# mother_bord.net
KiCad netlist of a schematic drawn in EAGLE
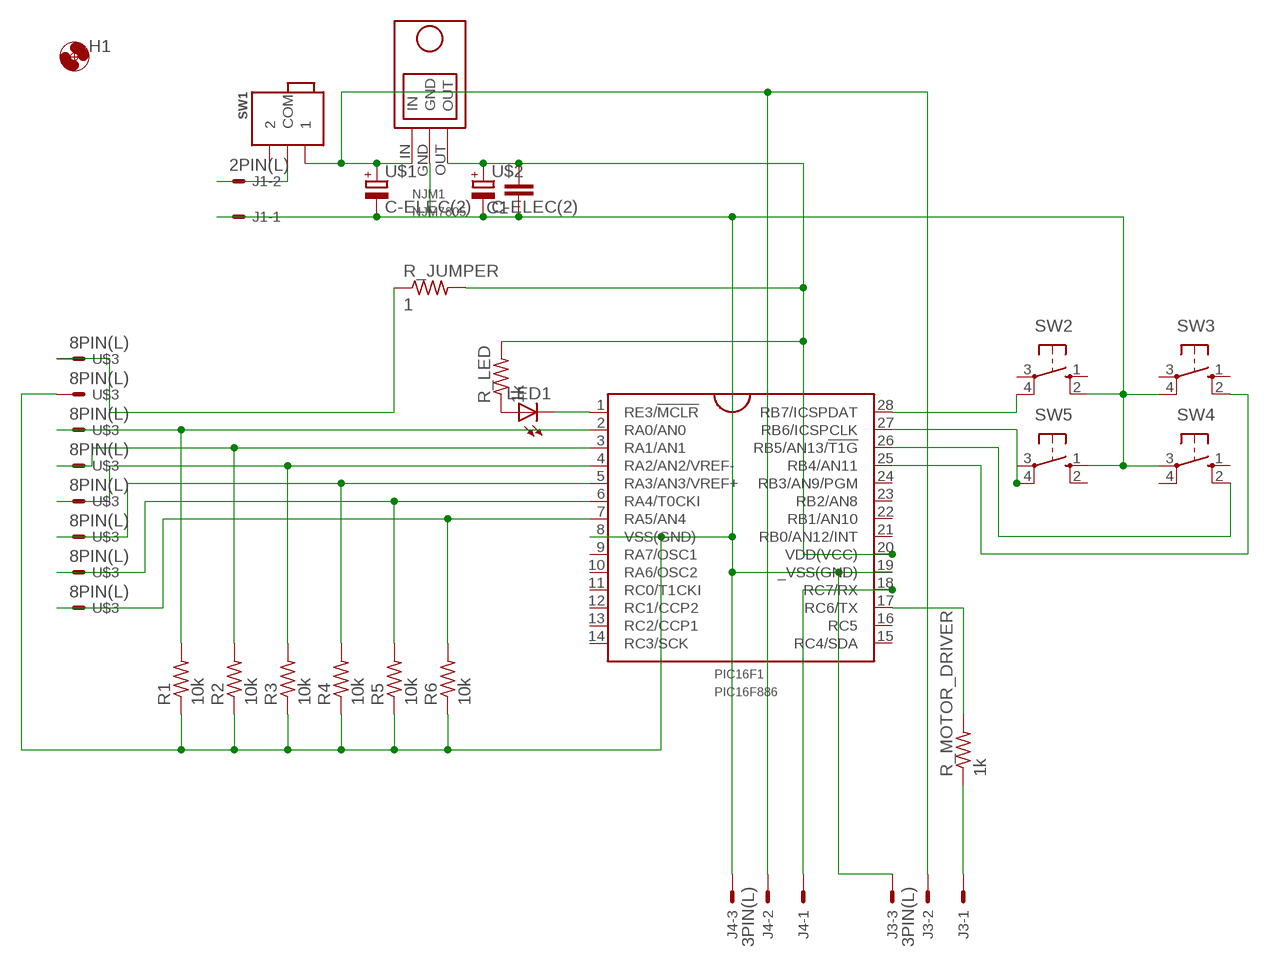
[diagram p0: schematic, sheet 1]

(export (version "E")
  (design (tool "Eeschema 10.0.6"))
  (components
    (comp (ref "C1")
      (value "C-3")
      (footprint "eagle-import:C-3")
      (libsource (lib "eagle-import") (part "C-3"))
    )
    (comp (ref "H1")
      (value "HOLE3.3M3BOLT")
      (footprint "eagle-import:HOLE3.3")
      (libsource (lib "eagle-import") (part "HOLE3.3M3BOLT"))
    )
    (comp (ref "J1")
      (value "2PIN(L)")
      (footprint "eagle-import:2PL")
      (libsource (lib "eagle-import") (part "2PIN(L)"))
    )
    (comp (ref "J3")
      (value "3PIN(L)")
      (footprint "eagle-import:3PL")
      (libsource (lib "eagle-import") (part "3PIN(L)"))
    )
    (comp (ref "J4")
      (value "3PIN(L)")
      (footprint "eagle-import:3PL")
      (libsource (lib "eagle-import") (part "3PIN(L)"))
    )
    (comp (ref "LED1")
      (value "LED-2")
      (footprint "eagle-import:LED5MM-2")
      (libsource (lib "eagle-import") (part "LED-2"))
    )
    (comp (ref "NJM1")
      (value "NJM7805")
      (footprint "eagle-import:NJM7805")
      (libsource (lib "eagle-import") (part "NJM7805"))
    )
    (comp (ref "PIC16F1")
      (value "PIC16F886")
      (footprint "eagle-import:DIL28-3")
      (libsource (lib "eagle-import") (part "PIC16F886"))
    )
    (comp (ref "R1")
      (value "10k")
      (footprint "eagle-import:0207_10")
      (libsource (lib "eagle-import") (part "R-"))
    )
    (comp (ref "R2")
      (value "10k")
      (footprint "eagle-import:0207_10")
      (libsource (lib "eagle-import") (part "R-"))
    )
    (comp (ref "R3")
      (value "10k")
      (footprint "eagle-import:0207_10")
      (libsource (lib "eagle-import") (part "R-"))
    )
    (comp (ref "R4")
      (value "10k")
      (footprint "eagle-import:0207_10")
      (libsource (lib "eagle-import") (part "R-"))
    )
    (comp (ref "R5")
      (value "10k")
      (footprint "eagle-import:0207_10")
      (libsource (lib "eagle-import") (part "R-"))
    )
    (comp (ref "R6")
      (value "10k")
      (footprint "eagle-import:0207_10")
      (libsource (lib "eagle-import") (part "R-"))
    )
    (comp (ref "R_JUMPER")
      (value "1")
      (footprint "eagle-import:0207_10")
      (libsource (lib "eagle-import") (part "R-"))
    )
    (comp (ref "R_LED")
      (value "1k")
      (footprint "eagle-import:0207_10")
      (libsource (lib "eagle-import") (part "R-"))
    )
    (comp (ref "R_MOTOR_DRIVER")
      (value "1k")
      (footprint "eagle-import:0207_10")
      (libsource (lib "eagle-import") (part "R-"))
    )
    (comp (ref "SW1")
      (value "SWITCH_MININORMAL")
      (footprint "eagle-import:SWITCH_MINI")
      (libsource (lib "eagle-import") (part "SWITCH_MININORMAL"))
    )
    (comp (ref "SW2")
      (value "TACTSW")
      (footprint "eagle-import:TACT")
      (libsource (lib "eagle-import") (part "TACTSW"))
    )
    (comp (ref "SW3")
      (value "TACTSW")
      (footprint "eagle-import:TACT")
      (libsource (lib "eagle-import") (part "TACTSW"))
    )
    (comp (ref "SW4")
      (value "TACTSW")
      (footprint "eagle-import:TACT")
      (libsource (lib "eagle-import") (part "TACTSW"))
    )
    (comp (ref "SW5")
      (value "TACTSW")
      (footprint "eagle-import:TACT")
      (libsource (lib "eagle-import") (part "TACTSW"))
    )
    (comp (ref "U$1")
      (value "C-ELEC(2)")
      (footprint "eagle-import:C-6MM(2)")
      (libsource (lib "eagle-import") (part "C-ELEC(2)"))
    )
    (comp (ref "U$2")
      (value "C-ELEC(2)")
      (footprint "eagle-import:C-6MM(2)")
      (libsource (lib "eagle-import") (part "C-ELEC(2)"))
    )
    (comp (ref "U$3")
      (value "8PIN(L)")
      (footprint "eagle-import:8PL")
      (libsource (lib "eagle-import") (part "8PIN(L)"))
    )
  )
  (nets
    (net (code "1") (name "/9V") (class "Default")
      (node (ref "J1") (pin "2") (pinfunction "S_2") (pintype "passive"))
      (node (ref "J3") (pin "2") (pinfunction "S_2") (pintype "passive"))
      (node (ref "J4") (pin "2") (pinfunction "S_2") (pintype "passive"))
      (node (ref "NJM1") (pin "IN") (pinfunction "IN_IN") (pintype "bidirectional"))
      (node (ref "SW1") (pin "1") (pinfunction "1_1") (pintype "passive"))
      (node (ref "SW1") (pin "COM") (pinfunction "COM_COM") (pintype "passive"))
      (node (ref "U$1") (pin "+") (pinfunction "+_+") (pintype "passive"))
    )
    (net (code "2") (name "Net-(J1A-S)") (class "Default")
      (node (ref "C1") (pin "1") (pinfunction "1_1") (pintype "passive"))
      (node (ref "J1") (pin "1") (pinfunction "S_1") (pintype "passive"))
      (node (ref "J3") (pin "3") (pinfunction "S_3") (pintype "passive"))
      (node (ref "J4") (pin "3") (pinfunction "S_3") (pintype "passive"))
      (node (ref "NJM1") (pin "GND") (pinfunction "GND_GND") (pintype "bidirectional"))
      (node (ref "PIC16F1") (pin "19") (pinfunction "_VSS(GND)_19") (pintype "power_in"))
      (node (ref "PIC16F1") (pin "8") (pinfunction "VSS(GND)_8") (pintype "power_in"))
      (node (ref "R1") (pin "1") (pinfunction "1_1") (pintype "passive"))
      (node (ref "R2") (pin "1") (pinfunction "1_1") (pintype "passive"))
      (node (ref "R3") (pin "1") (pinfunction "1_1") (pintype "passive"))
      (node (ref "R4") (pin "1") (pinfunction "1_1") (pintype "passive"))
      (node (ref "R5") (pin "1") (pinfunction "1_1") (pintype "passive"))
      (node (ref "R6") (pin "1") (pinfunction "1_1") (pintype "passive"))
      (node (ref "SW2") (pin "2") (pinfunction "S1_2") (pintype "passive"))
      (node (ref "SW3") (pin "4") (pinfunction "P1_4") (pintype "passive"))
      (node (ref "SW4") (pin "3") (pinfunction "P_3") (pintype "passive"))
      (node (ref "SW5") (pin "1") (pinfunction "S_1") (pintype "passive"))
      (node (ref "U$1") (pin "-") (pinfunction "-_-") (pintype "passive"))
      (node (ref "U$2") (pin "-") (pinfunction "-_-") (pintype "passive"))
      (node (ref "U$3") (pin "P7") (pinfunction "P7_P7") (pintype "passive"))
    )
    (net (code "3") (name "Net-(J3A-S)") (class "Default")
      (node (ref "J3") (pin "1") (pinfunction "S_1") (pintype "passive"))
      (node (ref "R_MOTOR_DRIVER") (pin "1") (pinfunction "1_1") (pintype "passive"))
    )
    (net (code "4") (name "Net-(J4A-S)") (class "Default")
      (node (ref "J4") (pin "1") (pinfunction "S_1") (pintype "passive"))
      (node (ref "PIC16F1") (pin "18") (pinfunction "RC7/RX_18") (pintype "bidirectional"))
    )
    (net (code "5") (name "Net-(LED1-C)") (class "Default")
      (node (ref "LED1") (pin "K") (pinfunction "C_K") (pintype "passive"))
      (node (ref "PIC16F1") (pin "1") (pinfunction "RE3/~{MCLR}_1") (pintype "bidirectional"))
    )
    (net (code "6") (name "Net-(LED1-PadA)") (class "Default")
      (node (ref "LED1") (pin "A") (pinfunction "A_A") (pintype "passive"))
      (node (ref "R_LED") (pin "1") (pinfunction "1_1") (pintype "passive"))
    )
    (net (code "7") (name "Net-(PIC16F1-RA0{slash}AN0)") (class "Default")
      (node (ref "PIC16F1") (pin "2") (pinfunction "RA0/AN0_2") (pintype "bidirectional"))
      (node (ref "R1") (pin "2") (pinfunction "2_2") (pintype "passive"))
      (node (ref "U$3") (pin "P6") (pinfunction "P6_P6") (pintype "passive"))
    )
    (net (code "8") (name "Net-(PIC16F1-RA1{slash}AN1)") (class "Default")
      (node (ref "PIC16F1") (pin "3") (pinfunction "RA1/AN1_3") (pintype "bidirectional"))
      (node (ref "R2") (pin "2") (pinfunction "2_2") (pintype "passive"))
      (node (ref "U$3") (pin "P5") (pinfunction "P5_P5") (pintype "passive"))
    )
    (net (code "9") (name "Net-(PIC16F1-RA2{slash}AN2{slash}VREF-)") (class "Default")
      (node (ref "PIC16F1") (pin "4") (pinfunction "RA2/AN2/VREF-_4") (pintype "bidirectional"))
      (node (ref "R3") (pin "2") (pinfunction "2_2") (pintype "passive"))
      (node (ref "U$3") (pin "P4") (pinfunction "P4_P4") (pintype "passive"))
    )
    (net (code "10") (name "Net-(PIC16F1-RA3{slash}AN3{slash}VREF+)") (class "Default")
      (node (ref "PIC16F1") (pin "5") (pinfunction "RA3/AN3/VREF+_5") (pintype "bidirectional"))
      (node (ref "R4") (pin "2") (pinfunction "2_2") (pintype "passive"))
      (node (ref "U$3") (pin "P3") (pinfunction "P3_P3") (pintype "passive"))
    )
    (net (code "11") (name "Net-(PIC16F1-RA4{slash}T0CKI)") (class "Default")
      (node (ref "PIC16F1") (pin "6") (pinfunction "RA4/T0CKI_6") (pintype "bidirectional"))
      (node (ref "R5") (pin "2") (pinfunction "2_2") (pintype "passive"))
      (node (ref "U$3") (pin "P2") (pinfunction "P2_P2") (pintype "passive"))
    )
    (net (code "12") (name "Net-(PIC16F1-RA5{slash}AN4)") (class "Default")
      (node (ref "PIC16F1") (pin "7") (pinfunction "RA5/AN4_7") (pintype "bidirectional"))
      (node (ref "R6") (pin "2") (pinfunction "2_2") (pintype "passive"))
      (node (ref "U$3") (pin "P1") (pinfunction "P1_P1") (pintype "passive"))
    )
    (net (code "13") (name "Net-(PIC16F1-RB4{slash}AN11)") (class "Default")
      (node (ref "PIC16F1") (pin "25") (pinfunction "RB4/AN11_25") (pintype "bidirectional"))
      (node (ref "SW3") (pin "2") (pinfunction "S1_2") (pintype "passive"))
    )
    (net (code "14") (name "Net-(PIC16F1-RB5{slash}AN13{slash}~{T1G})") (class "Default")
      (node (ref "PIC16F1") (pin "26") (pinfunction "RB5/AN13/~{T1G}_26") (pintype "bidirectional"))
      (node (ref "SW4") (pin "2") (pinfunction "S1_2") (pintype "passive"))
    )
    (net (code "15") (name "Net-(PIC16F1-RB6{slash}ICSPCLK)") (class "Default")
      (node (ref "PIC16F1") (pin "27") (pinfunction "RB6/ICSPCLK_27") (pintype "bidirectional"))
      (node (ref "SW5") (pin "4") (pinfunction "P1_4") (pintype "passive"))
    )
    (net (code "16") (name "Net-(PIC16F1-RB7{slash}ICSPDAT)") (class "Default")
      (node (ref "PIC16F1") (pin "28") (pinfunction "RB7/ICSPDAT_28") (pintype "bidirectional"))
      (node (ref "SW2") (pin "4") (pinfunction "P1_4") (pintype "passive"))
    )
    (net (code "17") (name "Net-(PIC16F1-RC6{slash}TX)") (class "Default")
      (node (ref "PIC16F1") (pin "17") (pinfunction "RC6/TX_17") (pintype "bidirectional"))
      (node (ref "R_MOTOR_DRIVER") (pin "2") (pinfunction "2_2") (pintype "passive"))
    )
    (net (code "18") (name "Net-(PIC16F1-VDD(VCC))") (class "Default")
      (node (ref "C1") (pin "2") (pinfunction "2_2") (pintype "passive"))
      (node (ref "NJM1") (pin "OUT") (pinfunction "OUT_OUT") (pintype "bidirectional"))
      (node (ref "PIC16F1") (pin "20") (pinfunction "VDD(VCC)_20") (pintype "power_in"))
      (node (ref "R_JUMPER") (pin "2") (pinfunction "2_2") (pintype "passive"))
      (node (ref "R_LED") (pin "2") (pinfunction "2_2") (pintype "passive"))
      (node (ref "U$2") (pin "+") (pinfunction "+_+") (pintype "passive"))
    )
    (net (code "19") (name "Net-(R_JUMPER-Pad1)") (class "Default")
      (node (ref "R_JUMPER") (pin "1") (pinfunction "1_1") (pintype "passive"))
      (node (ref "U$3") (pin "P8") (pinfunction "P8_P8") (pintype "passive"))
    )
    (net (code "20") (name "unconnected-(PIC16F1-RA6{slash}OSC2-Pad10)") (class "Default")
      (node (ref "PIC16F1") (pin "10") (pinfunction "RA6/OSC2_10") (pintype "bidirectional"))
    )
    (net (code "21") (name "unconnected-(PIC16F1-RA7{slash}OSC1-Pad9)") (class "Default")
      (node (ref "PIC16F1") (pin "9") (pinfunction "RA7/OSC1_9") (pintype "bidirectional"))
    )
    (net (code "22") (name "unconnected-(PIC16F1-RB0{slash}AN12{slash}INT-Pad21)") (class "Default")
      (node (ref "PIC16F1") (pin "21") (pinfunction "RB0/AN12/INT_21") (pintype "bidirectional"))
    )
    (net (code "23") (name "unconnected-(PIC16F1-RB1{slash}AN10-Pad22)") (class "Default")
      (node (ref "PIC16F1") (pin "22") (pinfunction "RB1/AN10_22") (pintype "bidirectional"))
    )
    (net (code "24") (name "unconnected-(PIC16F1-RB2{slash}AN8-Pad23)") (class "Default")
      (node (ref "PIC16F1") (pin "23") (pinfunction "RB2/AN8_23") (pintype "bidirectional"))
    )
    (net (code "25") (name "unconnected-(PIC16F1-RB3{slash}AN9{slash}PGM-Pad24)") (class "Default")
      (node (ref "PIC16F1") (pin "24") (pinfunction "RB3/AN9/PGM_24") (pintype "bidirectional"))
    )
    (net (code "26") (name "unconnected-(PIC16F1-RC0{slash}T1CKI-Pad11)") (class "Default")
      (node (ref "PIC16F1") (pin "11") (pinfunction "RC0/T1CKI_11") (pintype "bidirectional"))
    )
    (net (code "27") (name "unconnected-(PIC16F1-RC1{slash}CCP2-Pad12)") (class "Default")
      (node (ref "PIC16F1") (pin "12") (pinfunction "RC1/CCP2_12") (pintype "bidirectional"))
    )
    (net (code "28") (name "unconnected-(PIC16F1-RC2{slash}CCP1-Pad13)") (class "Default")
      (node (ref "PIC16F1") (pin "13") (pinfunction "RC2/CCP1_13") (pintype "bidirectional"))
    )
    (net (code "29") (name "unconnected-(PIC16F1-RC3{slash}SCK-Pad14)") (class "Default")
      (node (ref "PIC16F1") (pin "14") (pinfunction "RC3/SCK_14") (pintype "bidirectional"))
    )
    (net (code "30") (name "unconnected-(PIC16F1-RC4{slash}SDA-Pad15)") (class "Default")
      (node (ref "PIC16F1") (pin "15") (pinfunction "RC4/SDA_15") (pintype "bidirectional"))
    )
    (net (code "31") (name "unconnected-(PIC16F1-RC5-Pad16)") (class "Default")
      (node (ref "PIC16F1") (pin "16") (pinfunction "RC5_16") (pintype "bidirectional"))
    )
    (net (code "32") (name "unconnected-(SW1-Pad2)") (class "Default")
      (node (ref "SW1") (pin "2") (pinfunction "2_2") (pintype "no_connect"))
    )
    (net (code "33") (name "unconnected-(SW2-P-Pad3)") (class "Default")
      (node (ref "SW2") (pin "3") (pinfunction "P_3") (pintype "passive"))
    )
    (net (code "34") (name "unconnected-(SW2-S-Pad1)") (class "Default")
      (node (ref "SW2") (pin "1") (pinfunction "S_1") (pintype "passive"))
    )
    (net (code "35") (name "unconnected-(SW3-P-Pad3)") (class "Default")
      (node (ref "SW3") (pin "3") (pinfunction "P_3") (pintype "passive"))
    )
    (net (code "36") (name "unconnected-(SW3-S-Pad1)") (class "Default")
      (node (ref "SW3") (pin "1") (pinfunction "S_1") (pintype "passive"))
    )
    (net (code "37") (name "unconnected-(SW4-P1-Pad4)") (class "Default")
      (node (ref "SW4") (pin "4") (pinfunction "P1_4") (pintype "passive"))
    )
    (net (code "38") (name "unconnected-(SW4-S-Pad1)") (class "Default")
      (node (ref "SW4") (pin "1") (pinfunction "S_1") (pintype "passive"))
    )
    (net (code "39") (name "unconnected-(SW5-P-Pad3)") (class "Default")
      (node (ref "SW5") (pin "3") (pinfunction "P_3") (pintype "passive"))
    )
    (net (code "40") (name "unconnected-(SW5-S1-Pad2)") (class "Default")
      (node (ref "SW5") (pin "2") (pinfunction "S1_2") (pintype "passive"))
    )
  )
)
